# 0219-carrier-for-0119-m328p.net
KiCad netlist of a schematic drawn in EAGLE
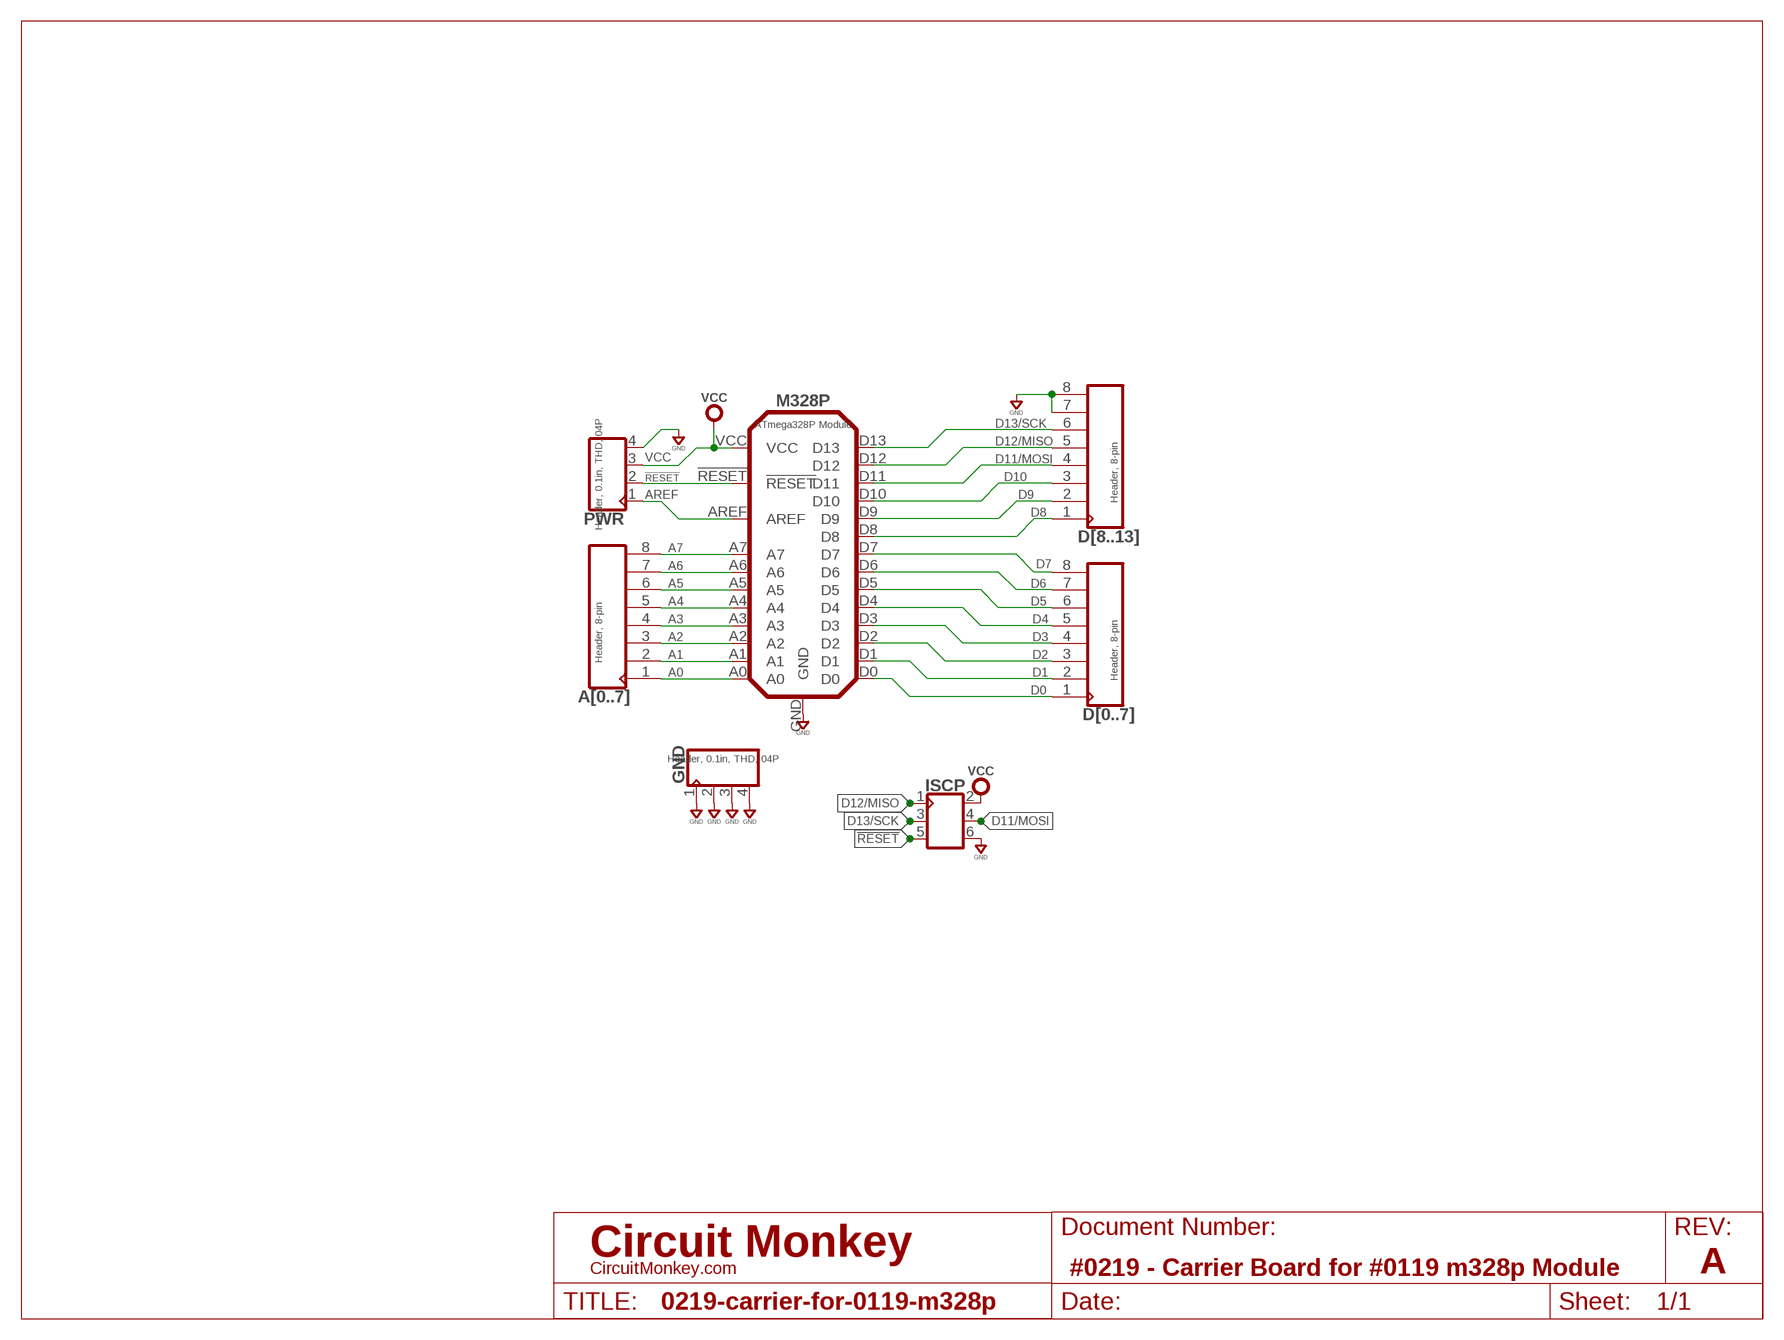
[diagram p0: schematic, sheet 1]

(export (version "E")
  (design (tool "Eeschema 10.0.6"))
  (components
    (comp (ref "A[0..7]")
      (value "Header, 8-pin")
      (footprint "eagle-import:MA08X1-VT-THD")
      (libsource (lib "eagle-import") (part "CON_08X1-VT-THD"))
    )
    (comp (ref "D[0..7]")
      (value "Header, 8-pin")
      (footprint "eagle-import:MA08X1-VT-THD")
      (libsource (lib "eagle-import") (part "CON_08X1-VT-THD"))
    )
    (comp (ref "D[8..13]")
      (value "Header, 8-pin")
      (footprint "eagle-import:MA08X1-VT-THD")
      (libsource (lib "eagle-import") (part "CON_08X1-VT-THD"))
    )
    (comp (ref "GND")
      (value "Header, 0.1in, THD, 04P")
      (footprint "eagle-import:MA04X1-VT-THD")
      (fields (field (name "MFR") "Molex") (field (name "MPN") "022284043"))
      (libsource (lib "eagle-import") (part "CON_04X1-THD-VT"))
    )
    (comp (ref "ISCP")
      (value "CON_03X2-VT_SMD")
      (footprint "eagle-import:MA03X2-VT-SMD")
      (libsource (lib "eagle-import") (part "CON_03X2-VT_SMD"))
    )
    (comp (ref "M328P")
      (value "ATmega328P Module")
      (footprint "eagle-import:0119A")
      (fields (field (name "MFR") "Circuit Monkey") (field (name "MPN") "0119A"))
      (libsource (lib "eagle-import") (part "0119REV-A"))
    )
    (comp (ref "PWR")
      (value "Header, 0.1in, THD, 04P")
      (footprint "eagle-import:MA04X1-VT-THD")
      (fields (field (name "MFR") "Molex") (field (name "MPN") "022284043"))
      (libsource (lib "eagle-import") (part "CON_04X1-THD-VT"))
    )
  )
  (nets
    (net (code "1") (name "/A0") (class "Default")
      (node (ref "A[0..7]") (pin "1") (pinfunction "1_1") (pintype "passive"))
      (node (ref "M328P") (pin "A0") (pinfunction "A0_A0") (pintype "bidirectional"))
    )
    (net (code "2") (name "/A1") (class "Default")
      (node (ref "A[0..7]") (pin "2") (pinfunction "2_2") (pintype "passive"))
      (node (ref "M328P") (pin "A1") (pinfunction "A1_A1") (pintype "bidirectional"))
    )
    (net (code "3") (name "/A2") (class "Default")
      (node (ref "A[0..7]") (pin "3") (pinfunction "3_3") (pintype "passive"))
      (node (ref "M328P") (pin "A2") (pinfunction "A2_A2") (pintype "bidirectional"))
    )
    (net (code "4") (name "/A3") (class "Default")
      (node (ref "A[0..7]") (pin "4") (pinfunction "4_4") (pintype "passive"))
      (node (ref "M328P") (pin "A3") (pinfunction "A3_A3") (pintype "bidirectional"))
    )
    (net (code "5") (name "/A4") (class "Default")
      (node (ref "A[0..7]") (pin "5") (pinfunction "5_5") (pintype "passive"))
      (node (ref "M328P") (pin "A4") (pinfunction "A4_A4") (pintype "bidirectional"))
    )
    (net (code "6") (name "/A5") (class "Default")
      (node (ref "A[0..7]") (pin "6") (pinfunction "6_6") (pintype "passive"))
      (node (ref "M328P") (pin "A5") (pinfunction "A5_A5") (pintype "bidirectional"))
    )
    (net (code "7") (name "/A6") (class "Default")
      (node (ref "A[0..7]") (pin "7") (pinfunction "7_7") (pintype "passive"))
      (node (ref "M328P") (pin "A6") (pinfunction "A6_A6") (pintype "bidirectional"))
    )
    (net (code "8") (name "/A7") (class "Default")
      (node (ref "A[0..7]") (pin "8") (pinfunction "8_8") (pintype "passive"))
      (node (ref "M328P") (pin "A7") (pinfunction "A7_A7") (pintype "bidirectional"))
    )
    (net (code "9") (name "/AREF") (class "Default")
      (node (ref "M328P") (pin "AREF") (pinfunction "AREF_AREF") (pintype "bidirectional"))
      (node (ref "PWR") (pin "1") (pinfunction "1_1") (pintype "passive"))
    )
    (net (code "10") (name "/D0") (class "Default")
      (node (ref "D[0..7]") (pin "1") (pinfunction "1_1") (pintype "passive"))
      (node (ref "M328P") (pin "D0") (pinfunction "D0_D0") (pintype "bidirectional"))
    )
    (net (code "11") (name "/D1") (class "Default")
      (node (ref "D[0..7]") (pin "2") (pinfunction "2_2") (pintype "passive"))
      (node (ref "M328P") (pin "D1") (pinfunction "D1_D1") (pintype "bidirectional"))
    )
    (net (code "12") (name "/D2") (class "Default")
      (node (ref "D[0..7]") (pin "3") (pinfunction "3_3") (pintype "passive"))
      (node (ref "M328P") (pin "D2") (pinfunction "D2_D2") (pintype "bidirectional"))
    )
    (net (code "13") (name "/D3") (class "Default")
      (node (ref "D[0..7]") (pin "4") (pinfunction "4_4") (pintype "passive"))
      (node (ref "M328P") (pin "D3") (pinfunction "D3_D3") (pintype "bidirectional"))
    )
    (net (code "14") (name "/D4") (class "Default")
      (node (ref "D[0..7]") (pin "5") (pinfunction "5_5") (pintype "passive"))
      (node (ref "M328P") (pin "D4") (pinfunction "D4_D4") (pintype "bidirectional"))
    )
    (net (code "15") (name "/D5") (class "Default")
      (node (ref "D[0..7]") (pin "6") (pinfunction "6_6") (pintype "passive"))
      (node (ref "M328P") (pin "D5") (pinfunction "D5_D5") (pintype "bidirectional"))
    )
    (net (code "16") (name "/D6") (class "Default")
      (node (ref "D[0..7]") (pin "7") (pinfunction "7_7") (pintype "passive"))
      (node (ref "M328P") (pin "D6") (pinfunction "D6_D6") (pintype "bidirectional"))
    )
    (net (code "17") (name "/D7") (class "Default")
      (node (ref "D[0..7]") (pin "8") (pinfunction "8_8") (pintype "passive"))
      (node (ref "M328P") (pin "D7") (pinfunction "D7_D7") (pintype "bidirectional"))
    )
    (net (code "18") (name "/D8") (class "Default")
      (node (ref "D[8..13]") (pin "1") (pinfunction "1_1") (pintype "passive"))
      (node (ref "M328P") (pin "D8") (pinfunction "D8_D8") (pintype "bidirectional"))
    )
    (net (code "19") (name "/D9") (class "Default")
      (node (ref "D[8..13]") (pin "2") (pinfunction "2_2") (pintype "passive"))
      (node (ref "M328P") (pin "D9") (pinfunction "D9_D9") (pintype "bidirectional"))
    )
    (net (code "20") (name "/D10") (class "Default")
      (node (ref "D[8..13]") (pin "3") (pinfunction "3_3") (pintype "passive"))
      (node (ref "M328P") (pin "D10") (pinfunction "D10_D10") (pintype "bidirectional"))
    )
    (net (code "21") (name "/~{RESET}") (class "Default")
      (node (ref "ISCP") (pin "5") (pinfunction "5_5") (pintype "passive"))
      (node (ref "M328P") (pin "!RESET") (pinfunction "~{RESET}_!RESET") (pintype "bidirectional"))
      (node (ref "PWR") (pin "2") (pinfunction "2_2") (pintype "passive"))
    )
    (net (code "22") (name "D11{slash}MOSI") (class "Default")
      (node (ref "D[8..13]") (pin "4") (pinfunction "4_4") (pintype "passive"))
      (node (ref "ISCP") (pin "4") (pinfunction "4_4") (pintype "passive"))
      (node (ref "M328P") (pin "D11") (pinfunction "D11_D11") (pintype "bidirectional"))
    )
    (net (code "23") (name "D12{slash}MISO") (class "Default")
      (node (ref "D[8..13]") (pin "5") (pinfunction "5_5") (pintype "passive"))
      (node (ref "ISCP") (pin "1") (pinfunction "1_1") (pintype "passive"))
      (node (ref "M328P") (pin "D12") (pinfunction "D12_D12") (pintype "bidirectional"))
    )
    (net (code "24") (name "D13{slash}SCK") (class "Default")
      (node (ref "D[8..13]") (pin "6") (pinfunction "6_6") (pintype "passive"))
      (node (ref "ISCP") (pin "3") (pinfunction "3_3") (pintype "passive"))
      (node (ref "M328P") (pin "D13") (pinfunction "D13_D13") (pintype "bidirectional"))
    )
    (net (code "25") (name "GND") (class "Default")
      (node (ref "D[8..13]") (pin "7") (pinfunction "7_7") (pintype "passive"))
      (node (ref "D[8..13]") (pin "8") (pinfunction "8_8") (pintype "passive"))
      (node (ref "GND") (pin "1") (pinfunction "1_1") (pintype "passive"))
      (node (ref "GND") (pin "2") (pinfunction "2_2") (pintype "passive"))
      (node (ref "GND") (pin "3") (pinfunction "3_3") (pintype "passive"))
      (node (ref "GND") (pin "4") (pinfunction "4_4") (pintype "passive"))
      (node (ref "ISCP") (pin "6") (pinfunction "6_6") (pintype "passive"))
      (node (ref "M328P") (pin "GND") (pinfunction "GND_GND") (pintype "bidirectional"))
      (node (ref "PWR") (pin "4") (pinfunction "4_4") (pintype "passive"))
    )
    (net (code "26") (name "VCC") (class "Default")
      (node (ref "ISCP") (pin "2") (pinfunction "2_2") (pintype "passive"))
      (node (ref "M328P") (pin "VCC") (pinfunction "VCC_VCC") (pintype "bidirectional"))
      (node (ref "PWR") (pin "3") (pinfunction "3_3") (pintype "passive"))
    )
  )
)
